# JTAG_ALTIUM_AUTO.net
KiCad netlist of a schematic drawn in Altium Designer
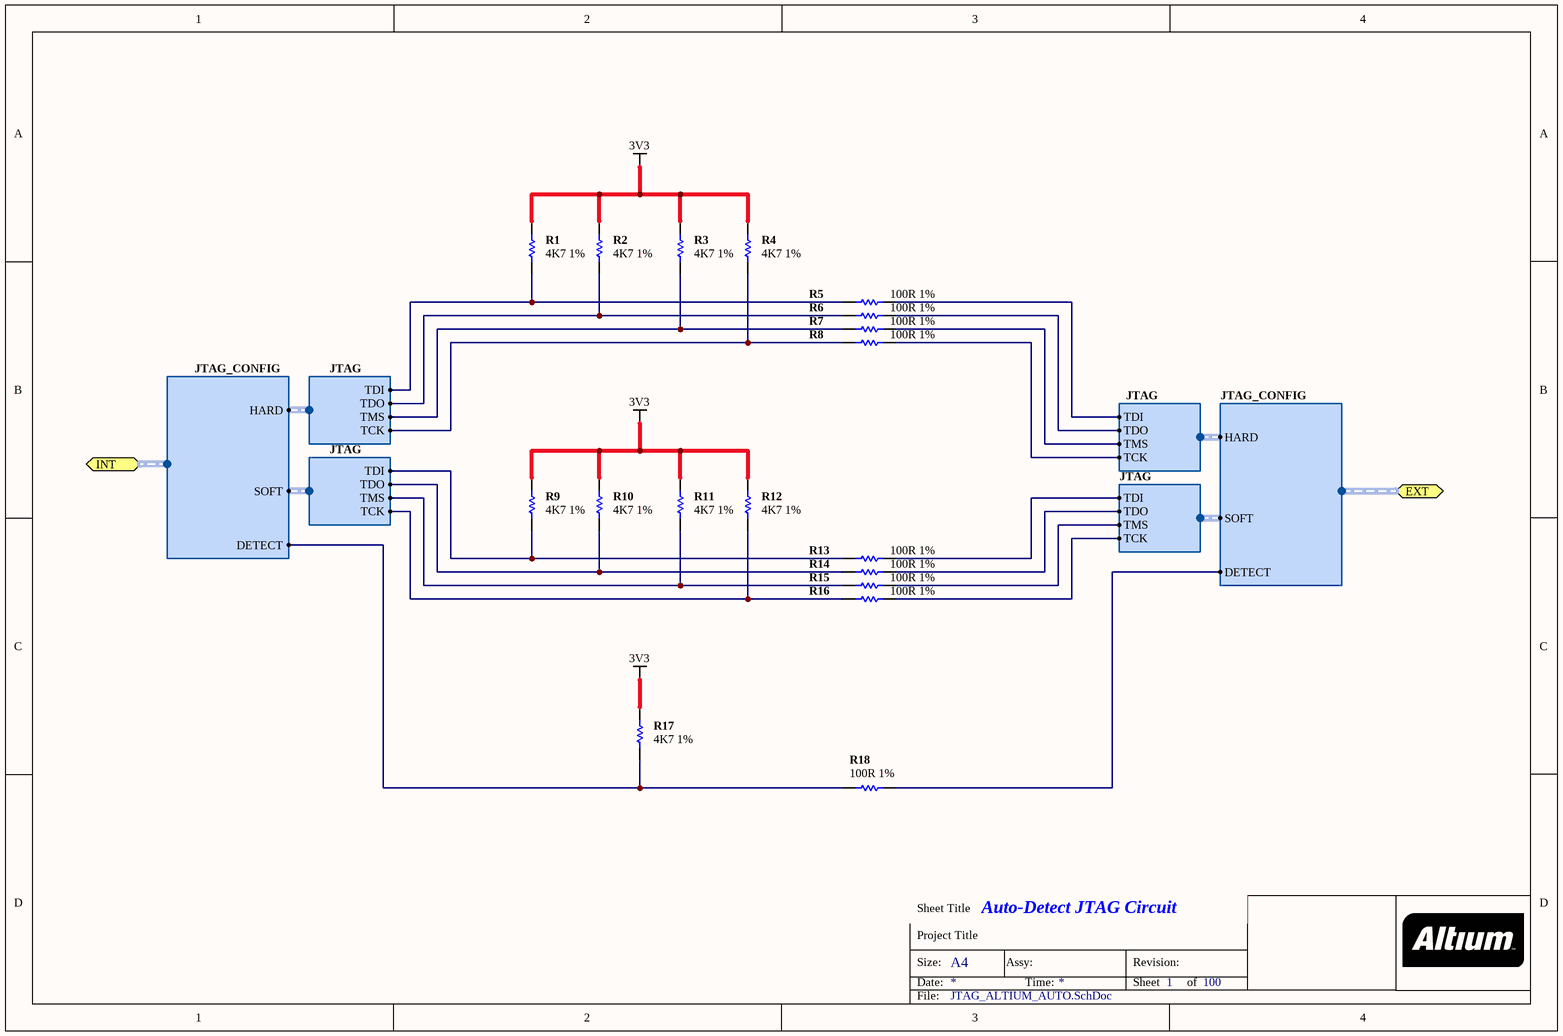
[diagram p0: JTAG_ALTIUM_AUTO.SchDoc]

(export (version "E")
  (design (tool "Eeschema 10.0.6"))
  (components
    (comp (ref "R1")
      (value "4K7 1%")
      (footprint "RESC1005-STAR")
      (description "Resistor, 4K7 1% 0402 (1005)")
      (fields (field (name "TOLERANCE") "1 %"))
      (libsource (lib "altium-import") (part "root_2_RES_"))
    )
    (comp (ref "R2")
      (value "4K7 1%")
      (footprint "RESC1005-STAR")
      (description "Resistor, 4K7 1% 0402 (1005)")
      (fields (field (name "TOLERANCE") "1 %"))
      (libsource (lib "altium-import") (part "root_2_RES_"))
    )
    (comp (ref "R3")
      (value "4K7 1%")
      (footprint "RESC1005-STAR")
      (description "Resistor, 4K7 1% 0402 (1005)")
      (fields (field (name "TOLERANCE") "1 %"))
      (libsource (lib "altium-import") (part "root_2_RES_"))
    )
    (comp (ref "R4")
      (value "4K7 1%")
      (footprint "RESC1005-STAR")
      (description "Resistor, 4K7 1% 0402 (1005)")
      (fields (field (name "TOLERANCE") "1 %"))
      (libsource (lib "altium-import") (part "root_2_RES_"))
    )
    (comp (ref "R5")
      (value "100R 1%")
      (footprint "RESC1005-STAR")
      (description "Resistor, 100R 1% 0402 (1005)")
      (fields (field (name "TOLERANCE") "1 %"))
      (libsource (lib "altium-import") (part "root_1_RES_"))
    )
    (comp (ref "R6")
      (value "100R 1%")
      (footprint "RESC1005-STAR")
      (description "Resistor, 100R 1% 0402 (1005)")
      (fields (field (name "TOLERANCE") "1 %"))
      (libsource (lib "altium-import") (part "root_1_RES_"))
    )
    (comp (ref "R7")
      (value "100R 1%")
      (footprint "RESC1005-STAR")
      (description "Resistor, 100R 1% 0402 (1005)")
      (fields (field (name "TOLERANCE") "1 %"))
      (libsource (lib "altium-import") (part "root_1_RES_"))
    )
    (comp (ref "R8")
      (value "100R 1%")
      (footprint "RESC1005-STAR")
      (description "Resistor, 100R 1% 0402 (1005)")
      (fields (field (name "TOLERANCE") "1 %"))
      (libsource (lib "altium-import") (part "root_1_RES_"))
    )
    (comp (ref "R9")
      (value "4K7 1%")
      (footprint "RESC1005-STAR")
      (description "Resistor, 4K7 1% 0402 (1005)")
      (fields (field (name "TOLERANCE") "1 %"))
      (libsource (lib "altium-import") (part "root_2_RES_"))
    )
    (comp (ref "R10")
      (value "4K7 1%")
      (footprint "RESC1005-STAR")
      (description "Resistor, 4K7 1% 0402 (1005)")
      (fields (field (name "TOLERANCE") "1 %"))
      (libsource (lib "altium-import") (part "root_2_RES_"))
    )
    (comp (ref "R11")
      (value "4K7 1%")
      (footprint "RESC1005-STAR")
      (description "Resistor, 4K7 1% 0402 (1005)")
      (fields (field (name "TOLERANCE") "1 %"))
      (libsource (lib "altium-import") (part "root_2_RES_"))
    )
    (comp (ref "R12")
      (value "4K7 1%")
      (footprint "RESC1005-STAR")
      (description "Resistor, 4K7 1% 0402 (1005)")
      (fields (field (name "TOLERANCE") "1 %"))
      (libsource (lib "altium-import") (part "root_2_RES_"))
    )
    (comp (ref "R13")
      (value "100R 1%")
      (footprint "RESC1005-STAR")
      (description "Resistor, 100R 1% 0402 (1005)")
      (fields (field (name "TOLERANCE") "1 %"))
      (libsource (lib "altium-import") (part "root_1_RES_"))
    )
    (comp (ref "R14")
      (value "100R 1%")
      (footprint "RESC1005-STAR")
      (description "Resistor, 100R 1% 0402 (1005)")
      (fields (field (name "TOLERANCE") "1 %"))
      (libsource (lib "altium-import") (part "root_1_RES_"))
    )
    (comp (ref "R15")
      (value "100R 1%")
      (footprint "RESC1005-STAR")
      (description "Resistor, 100R 1% 0402 (1005)")
      (fields (field (name "TOLERANCE") "1 %"))
      (libsource (lib "altium-import") (part "root_1_RES_"))
    )
    (comp (ref "R16")
      (value "100R 1%")
      (footprint "RESC1005-STAR")
      (description "Resistor, 100R 1% 0402 (1005)")
      (fields (field (name "TOLERANCE") "1 %"))
      (libsource (lib "altium-import") (part "root_1_RES_"))
    )
    (comp (ref "R17")
      (value "4K7 1%")
      (footprint "RESC1005-STAR")
      (description "Resistor, 4K7 1% 0402 (1005)")
      (fields (field (name "TOLERANCE") "1 %"))
      (libsource (lib "AltiumDesignLibrary") (part "RES"))
    )
    (comp (ref "R18")
      (value "100R 1%")
      (footprint "RESC1005-STAR")
      (description "Resistor, 100R 1% 0402 (1005)")
      (fields (field (name "TOLERANCE") "1 %"))
      (libsource (lib "altium-import") (part "root_1_RES_"))
    )
  )
  (nets
    (net (code "7") (name "3V3") (class "Default")
      (node (ref "R1") (pin "2") (pinfunction "2_2") (pintype "passive"))
      (node (ref "R10") (pin "2") (pinfunction "2_2") (pintype "passive"))
      (node (ref "R11") (pin "2") (pinfunction "2_2") (pintype "passive"))
      (node (ref "R12") (pin "2") (pinfunction "2_2") (pintype "passive"))
      (node (ref "R17") (pin "2") (pinfunction "2_2") (pintype "passive"))
      (node (ref "R2") (pin "2") (pinfunction "2_2") (pintype "passive"))
      (node (ref "R3") (pin "2") (pinfunction "2_2") (pintype "passive"))
      (node (ref "R4") (pin "2") (pinfunction "2_2") (pintype "passive"))
      (node (ref "R9") (pin "2") (pinfunction "2_2") (pintype "passive"))
    )
    (net (code "8") (name "Net-(R1-Pad1)") (class "Default")
      (node (ref "R1") (pin "1") (pinfunction "1_1") (pintype "passive"))
      (node (ref "R5") (pin "1") (pinfunction "1_1") (pintype "passive"))
    )
    (net (code "9") (name "Net-(R2-Pad1)") (class "Default")
      (node (ref "R2") (pin "1") (pinfunction "1_1") (pintype "passive"))
      (node (ref "R6") (pin "1") (pinfunction "1_1") (pintype "passive"))
    )
    (net (code "10") (name "Net-(R3-Pad1)") (class "Default")
      (node (ref "R3") (pin "1") (pinfunction "1_1") (pintype "passive"))
      (node (ref "R7") (pin "1") (pinfunction "1_1") (pintype "passive"))
    )
    (net (code "11") (name "Net-(R4-Pad1)") (class "Default")
      (node (ref "R4") (pin "1") (pinfunction "1_1") (pintype "passive"))
      (node (ref "R8") (pin "1") (pinfunction "1_1") (pintype "passive"))
    )
    (net (code "12") (name "Net-(R10-Pad1)") (class "Default")
      (node (ref "R10") (pin "1") (pinfunction "1_1") (pintype "passive"))
      (node (ref "R14") (pin "1") (pinfunction "1_1") (pintype "passive"))
    )
    (net (code "13") (name "Net-(R11-Pad1)") (class "Default")
      (node (ref "R11") (pin "1") (pinfunction "1_1") (pintype "passive"))
      (node (ref "R15") (pin "1") (pinfunction "1_1") (pintype "passive"))
    )
    (net (code "14") (name "Net-(R12-Pad1)") (class "Default")
      (node (ref "R12") (pin "1") (pinfunction "1_1") (pintype "passive"))
      (node (ref "R16") (pin "1") (pinfunction "1_1") (pintype "passive"))
    )
    (net (code "15") (name "Net-(R13-Pad1)") (class "Default")
      (node (ref "R13") (pin "1") (pinfunction "1_1") (pintype "passive"))
      (node (ref "R9") (pin "1") (pinfunction "1_1") (pintype "passive"))
    )
    (net (code "16") (name "Net-(R17-Pad1)") (class "Default")
      (node (ref "R17") (pin "1") (pinfunction "1_1") (pintype "passive"))
      (node (ref "R18") (pin "1") (pinfunction "1_1") (pintype "passive"))
    )
    (net (code "17") (name "unconnected-(R5-Pad2)") (class "Default")
      (node (ref "R5") (pin "2") (pinfunction "2_2") (pintype "passive"))
    )
    (net (code "18") (name "unconnected-(R6-Pad2)") (class "Default")
      (node (ref "R6") (pin "2") (pinfunction "2_2") (pintype "passive"))
    )
    (net (code "19") (name "unconnected-(R7-Pad2)") (class "Default")
      (node (ref "R7") (pin "2") (pinfunction "2_2") (pintype "passive"))
    )
    (net (code "20") (name "unconnected-(R8-Pad2)") (class "Default")
      (node (ref "R8") (pin "2") (pinfunction "2_2") (pintype "passive"))
    )
    (net (code "21") (name "unconnected-(R13-Pad2)") (class "Default")
      (node (ref "R13") (pin "2") (pinfunction "2_2") (pintype "passive"))
    )
    (net (code "22") (name "unconnected-(R14-Pad2)") (class "Default")
      (node (ref "R14") (pin "2") (pinfunction "2_2") (pintype "passive"))
    )
    (net (code "23") (name "unconnected-(R15-Pad2)") (class "Default")
      (node (ref "R15") (pin "2") (pinfunction "2_2") (pintype "passive"))
    )
    (net (code "24") (name "unconnected-(R16-Pad2)") (class "Default")
      (node (ref "R16") (pin "2") (pinfunction "2_2") (pintype "passive"))
    )
    (net (code "25") (name "unconnected-(R18-Pad2)") (class "Default")
      (node (ref "R18") (pin "2") (pinfunction "2_2") (pintype "passive"))
    )
  )
)
